# ADC.net
KiCad netlist of a schematic drawn in Altium Designer
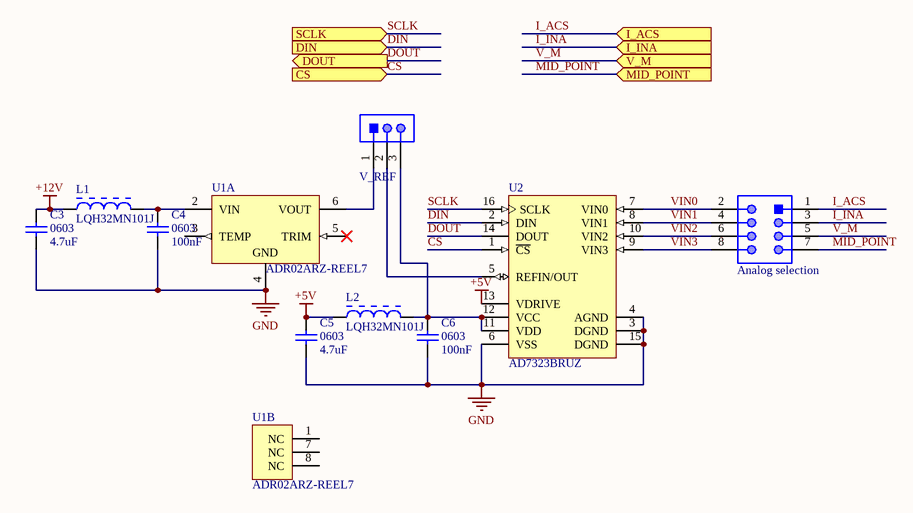
[diagram p0: ADC.SchDoc]

(export (version "E")
  (design (tool "Eeschema 10.0.6"))
  (components
    (comp (ref "Analog selection")
      (value "61300821121")
      (footprint "61300821121")
      (description "THT Vertical Pin Header WR-PHD, Pitch 2.54 mm, Dual Row, 8 pins")
      (fields (field (name "MANUFACTURER") "Wurth Elektronik") (field (name "PUBLISHER") "WurthElektronik"))
      (libsource (lib "Altium Content Vault") (part "WE-CN-2P-M-R8"))
    )
    (comp (ref "C3")
      (value "4.7uF")
      (footprint "CAPC0603(1608)55_M")
      (description "CAP 4.7uF 10V ±20% 0603 (1608 Metric) Thickness 0.55mm SMD")
      (fields
        (field (name "TOLERANCE") "Â±20%")
        (field (name "CASE-EIA") "0603")
        (field (name "Comment") "CAP 4.7uF 10V 0603(1608)")
      )
      (libsource (lib "Altium Content Vault") (part "CMP-1035-02786-1"))
    )
    (comp (ref "C4")
      (value "100nF")
      (footprint "CAPC0603(1608)100_M")
      (description "CAP 100nF 10V ±20% 0603 (1608 Metric) Thickness 1mm SMD")
      (fields
        (field (name "TOLERANCE") "Â±20%")
        (field (name "CASE-EIA") "0603")
        (field (name "Comment") "CAP 100nF 10V 0603(1608)")
      )
      (libsource (lib "Altium Content Vault") (part "CMP-1035-02581-1"))
    )
    (comp (ref "C5")
      (value "4.7uF")
      (footprint "CAPC0603(1608)55_M")
      (description "CAP 4.7uF 10V ±20% 0603 (1608 Metric) Thickness 0.55mm SMD")
      (fields
        (field (name "TOLERANCE") "Â±20%")
        (field (name "CASE-EIA") "0603")
        (field (name "Comment") "CAP 4.7uF 10V 0603(1608)")
      )
      (libsource (lib "Altium Content Vault") (part "CMP-1035-02786-1"))
    )
    (comp (ref "C6")
      (value "100nF")
      (footprint "CAPC0603(1608)100_M")
      (description "CAP 100nF 10V ±20% 0603 (1608 Metric) Thickness 1mm SMD")
      (fields
        (field (name "TOLERANCE") "Â±20%")
        (field (name "CASE-EIA") "0603")
        (field (name "Comment") "CAP 100nF 10V 0603(1608)")
      )
      (libsource (lib "Altium Content Vault") (part "CMP-1035-02581-1"))
    )
    (comp (ref "L1")
      (value "CM311411-101KL")
      (footprint "BOUR-SRN3015-2_V")
      (fields
        (field (name "MANUFACTURER") "Bourns")
        (field (name "PARTNUMBER") "SRN3015-101M")
        (field (name "COMMENT_1") "LQH32MN101J")
      )
      (libsource (lib "Altium Content Vault") (part "CMP-0007-00009-1"))
    )
    (comp (ref "L2")
      (value "CM311411-101KL")
      (footprint "BOUR-SRN3015-2_V")
      (fields
        (field (name "MANUFACTURER") "Bourns")
        (field (name "PARTNUMBER") "SRN3015-101M")
        (field (name "COMMENT_1") "LQH32MN101J")
      )
      (libsource (lib "Altium Content Vault") (part "CMP-0007-00009-1"))
    )
    (comp (ref "U1")
      (value "ADR02ARZ-REEL7")
      (footprint "ADI-R-8_L")
      (fields (field (name "MANUFACTURER") "Analog Devices"))
      (libsource (lib "Altium Content Vault") (part "ADI-REF0x_ADR0x-X-8"))
    )
    (comp (ref "U2")
      (value "AD7323BRUZ")
      (footprint "RU-16_N")
      (fields (field (name "MANUFACTURER") "Analog Devices") (field (name "GENERIC PART NUMBER") "AD7323"))
      (libsource (lib "Altium Content Vault") (part "ADI-AD7323-RU-16"))
    )
    (comp (ref "V_REF")
      (value "61300311121")
      (footprint "61300311121")
      (description "THT Vertical Pin Header WR-PHD, Pitch 2.54 mm, Single Row, 3 pins")
      (fields (field (name "MANUFACTURER") "Wurth Elektronik") (field (name "PUBLISHER") "WurthElektronik"))
      (libsource (lib "Altium Content Vault") (part "WE-CN-1P-M-R3"))
    )
  )
  (nets
    (net (code "1") (name "+5V") (class "Default")
      (node (ref "C5") (pin "2") (pinfunction "2_2") (pintype "passive"))
      (node (ref "L2") (pin "1") (pinfunction "1_1") (pintype "passive"))
      (node (ref "U2") (pin "13") (pinfunction "VDRIVE_13") (pintype "power_in"))
    )
    (net (code "2") (name "+12V") (class "Default")
      (node (ref "C3") (pin "2") (pinfunction "2_2") (pintype "passive"))
      (node (ref "L1") (pin "1") (pinfunction "1_1") (pintype "passive"))
    )
    (net (code "3") (name "/CS") (class "Default")
      (node (ref "U2") (pin "1") (pinfunction "~{CS}_1") (pintype "input"))
    )
    (net (code "4") (name "/DIN") (class "Default")
      (node (ref "U2") (pin "2") (pinfunction "DIN_2") (pintype "input"))
    )
    (net (code "5") (name "/DOUT") (class "Default")
      (node (ref "U2") (pin "14") (pinfunction "DOUT_14") (pintype "tri_state"))
    )
    (net (code "6") (name "/I_ACS") (class "Default")
      (node (ref "Analog selection") (pin "1") (pinfunction "1_1") (pintype "passive"))
    )
    (net (code "7") (name "/I_INA") (class "Default")
      (node (ref "Analog selection") (pin "3") (pinfunction "3_3") (pintype "passive"))
    )
    (net (code "8") (name "/MID_POINT") (class "Default")
      (node (ref "Analog selection") (pin "7") (pinfunction "7_7") (pintype "passive"))
    )
    (net (code "9") (name "/SCLK") (class "Default")
      (node (ref "U2") (pin "16") (pinfunction "SCLK_16") (pintype "input"))
    )
    (net (code "10") (name "/VIN0") (class "Default")
      (node (ref "Analog selection") (pin "2") (pinfunction "2_2") (pintype "passive"))
      (node (ref "U2") (pin "7") (pinfunction "VIN0_7") (pintype "input"))
    )
    (net (code "11") (name "/VIN1") (class "Default")
      (node (ref "Analog selection") (pin "4") (pinfunction "4_4") (pintype "passive"))
      (node (ref "U2") (pin "8") (pinfunction "VIN1_8") (pintype "input"))
    )
    (net (code "12") (name "/VIN2") (class "Default")
      (node (ref "Analog selection") (pin "6") (pinfunction "6_6") (pintype "passive"))
      (node (ref "U2") (pin "10") (pinfunction "VIN2_10") (pintype "input"))
    )
    (net (code "13") (name "/VIN3") (class "Default")
      (node (ref "Analog selection") (pin "8") (pinfunction "8_8") (pintype "passive"))
      (node (ref "U2") (pin "9") (pinfunction "VIN3_9") (pintype "input"))
    )
    (net (code "14") (name "/V_M") (class "Default")
      (node (ref "Analog selection") (pin "5") (pinfunction "5_5") (pintype "passive"))
    )
    (net (code "15") (name "GND") (class "Default")
      (node (ref "C3") (pin "1") (pinfunction "1_1") (pintype "passive"))
      (node (ref "C4") (pin "1") (pinfunction "1_1") (pintype "passive"))
      (node (ref "C5") (pin "1") (pinfunction "1_1") (pintype "passive"))
      (node (ref "C6") (pin "1") (pinfunction "1_1") (pintype "passive"))
      (node (ref "U1") (pin "4") (pinfunction "GND_4") (pintype "power_in"))
      (node (ref "U2") (pin "15") (pinfunction "DGND_15") (pintype "power_in"))
      (node (ref "U2") (pin "3") (pinfunction "DGND_3") (pintype "power_in"))
      (node (ref "U2") (pin "4") (pinfunction "AGND_4") (pintype "power_in"))
      (node (ref "U2") (pin "6") (pinfunction "VSS_6") (pintype "power_in"))
    )
    (net (code "16") (name "Net-(U1A-VIN)") (class "Default")
      (node (ref "C4") (pin "2") (pinfunction "2_2") (pintype "passive"))
      (node (ref "L1") (pin "2") (pinfunction "2_2") (pintype "passive"))
      (node (ref "U1") (pin "2") (pinfunction "VIN_2") (pintype "power_in"))
    )
    (net (code "17") (name "Net-(U1A-VOUT)") (class "Default")
      (node (ref "U1") (pin "6") (pinfunction "VOUT_6") (pintype "power_in"))
      (node (ref "V_REF") (pin "1") (pinfunction "1_1") (pintype "passive"))
    )
    (net (code "18") (name "Net-(U2-REFIN{slash}OUT)") (class "Default")
      (node (ref "U2") (pin "5") (pinfunction "REFIN/OUT_5") (pintype "bidirectional"))
      (node (ref "V_REF") (pin "2") (pinfunction "2_2") (pintype "passive"))
    )
    (net (code "19") (name "Net-(U2-VCC)") (class "Default")
      (node (ref "C6") (pin "2") (pinfunction "2_2") (pintype "passive"))
      (node (ref "L2") (pin "2") (pinfunction "2_2") (pintype "passive"))
      (node (ref "U2") (pin "11") (pinfunction "VDD_11") (pintype "power_in"))
      (node (ref "U2") (pin "12") (pinfunction "VCC_12") (pintype "power_in"))
      (node (ref "V_REF") (pin "3") (pinfunction "3_3") (pintype "passive"))
    )
    (net (code "20") (name "unconnected-(U1A-TEMP-Pad3)") (class "Default")
      (node (ref "U1") (pin "3") (pinfunction "TEMP_3") (pintype "output"))
    )
    (net (code "21") (name "unconnected-(U1A-TRIM-Pad5)") (class "Default")
      (node (ref "U1") (pin "5") (pinfunction "TRIM_5") (pintype "input+no_connect"))
    )
    (net (code "22") (name "unconnected-(U1B-NC-Pad1)") (class "Default")
      (node (ref "U1") (pin "1") (pinfunction "NC_1") (pintype "passive"))
    )
    (net (code "23") (name "unconnected-(U1B-NC-Pad7)") (class "Default")
      (node (ref "U1") (pin "7") (pinfunction "NC_7") (pintype "passive"))
    )
    (net (code "24") (name "unconnected-(U1B-NC-Pad8)") (class "Default")
      (node (ref "U1") (pin "8") (pinfunction "NC_8") (pintype "passive"))
    )
  )
)
